# 2v5_Regulator.net
KiCad netlist of a schematic drawn in Altium Designer
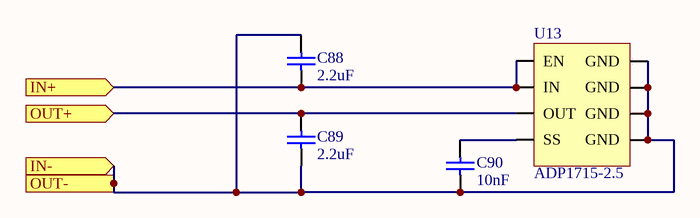
[diagram p0: 2v5_Regulator.SchDoc]

(export (version "E")
  (design (tool "Eeschema 10.0.6"))
  (components
    (comp (ref "C88")
      (value "2.2uF")
      (footprint "0402_Cap")
      (description "Capacitor, 2.2uF, 0805")
      (libsource (lib "Arturo_Approved") (part "CL21A225KAFNNNE"))
    )
    (comp (ref "C89")
      (value "2.2uF")
      (footprint "0402_Cap")
      (description "Capacitor, 2.2uF, 0805")
      (libsource (lib "Arturo_Approved") (part "CL21A225KAFNNNE"))
    )
    (comp (ref "C90")
      (value "10nF")
      (footprint "0402_Cap")
      (description "Capacitor, 10nF, 0805")
      (libsource (lib "Arturo_Approved") (part "C0805C103K1RAC7210"))
    )
    (comp (ref "U13")
      (value "ADP1715-2.5")
      (footprint "MSOP_8")
      (description "2.5V linear regulator")
      (libsource (lib "Arturo_Approved") (part "ADP1715ARMZ-2.5-R7"))
    )
  )
  (nets
    (net (code "1") (name "/IN+") (class "Default")
      (node (ref "C88") (pin "1") (pinfunction "1_1") (pintype "passive"))
      (node (ref "U13") (pin "1") (pinfunction "EN_1") (pintype "passive"))
      (node (ref "U13") (pin "2") (pinfunction "IN_2") (pintype "passive"))
    )
    (net (code "2") (name "/IN-") (class "Default")
      (node (ref "C88") (pin "2") (pinfunction "2_2") (pintype "passive"))
      (node (ref "C89") (pin "1") (pinfunction "1_1") (pintype "passive"))
      (node (ref "C90") (pin "1") (pinfunction "1_1") (pintype "passive"))
      (node (ref "U13") (pin "5") (pinfunction "GND_5") (pintype "passive"))
      (node (ref "U13") (pin "6") (pinfunction "GND_6") (pintype "passive"))
      (node (ref "U13") (pin "7") (pinfunction "GND_7") (pintype "passive"))
      (node (ref "U13") (pin "8") (pinfunction "GND_8") (pintype "passive"))
    )
    (net (code "3") (name "/OUT+") (class "Default")
      (node (ref "C89") (pin "2") (pinfunction "2_2") (pintype "passive"))
      (node (ref "U13") (pin "3") (pinfunction "OUT_3") (pintype "passive"))
    )
    (net (code "4") (name "Net-(U13-SS)") (class "Default")
      (node (ref "C90") (pin "2") (pinfunction "2_2") (pintype "passive"))
      (node (ref "U13") (pin "4") (pinfunction "SS_4") (pintype "passive"))
    )
  )
)
